# eco_mthbrd_REV_C1_sch.net
KiCad netlist of a schematic drawn in Altium Designer
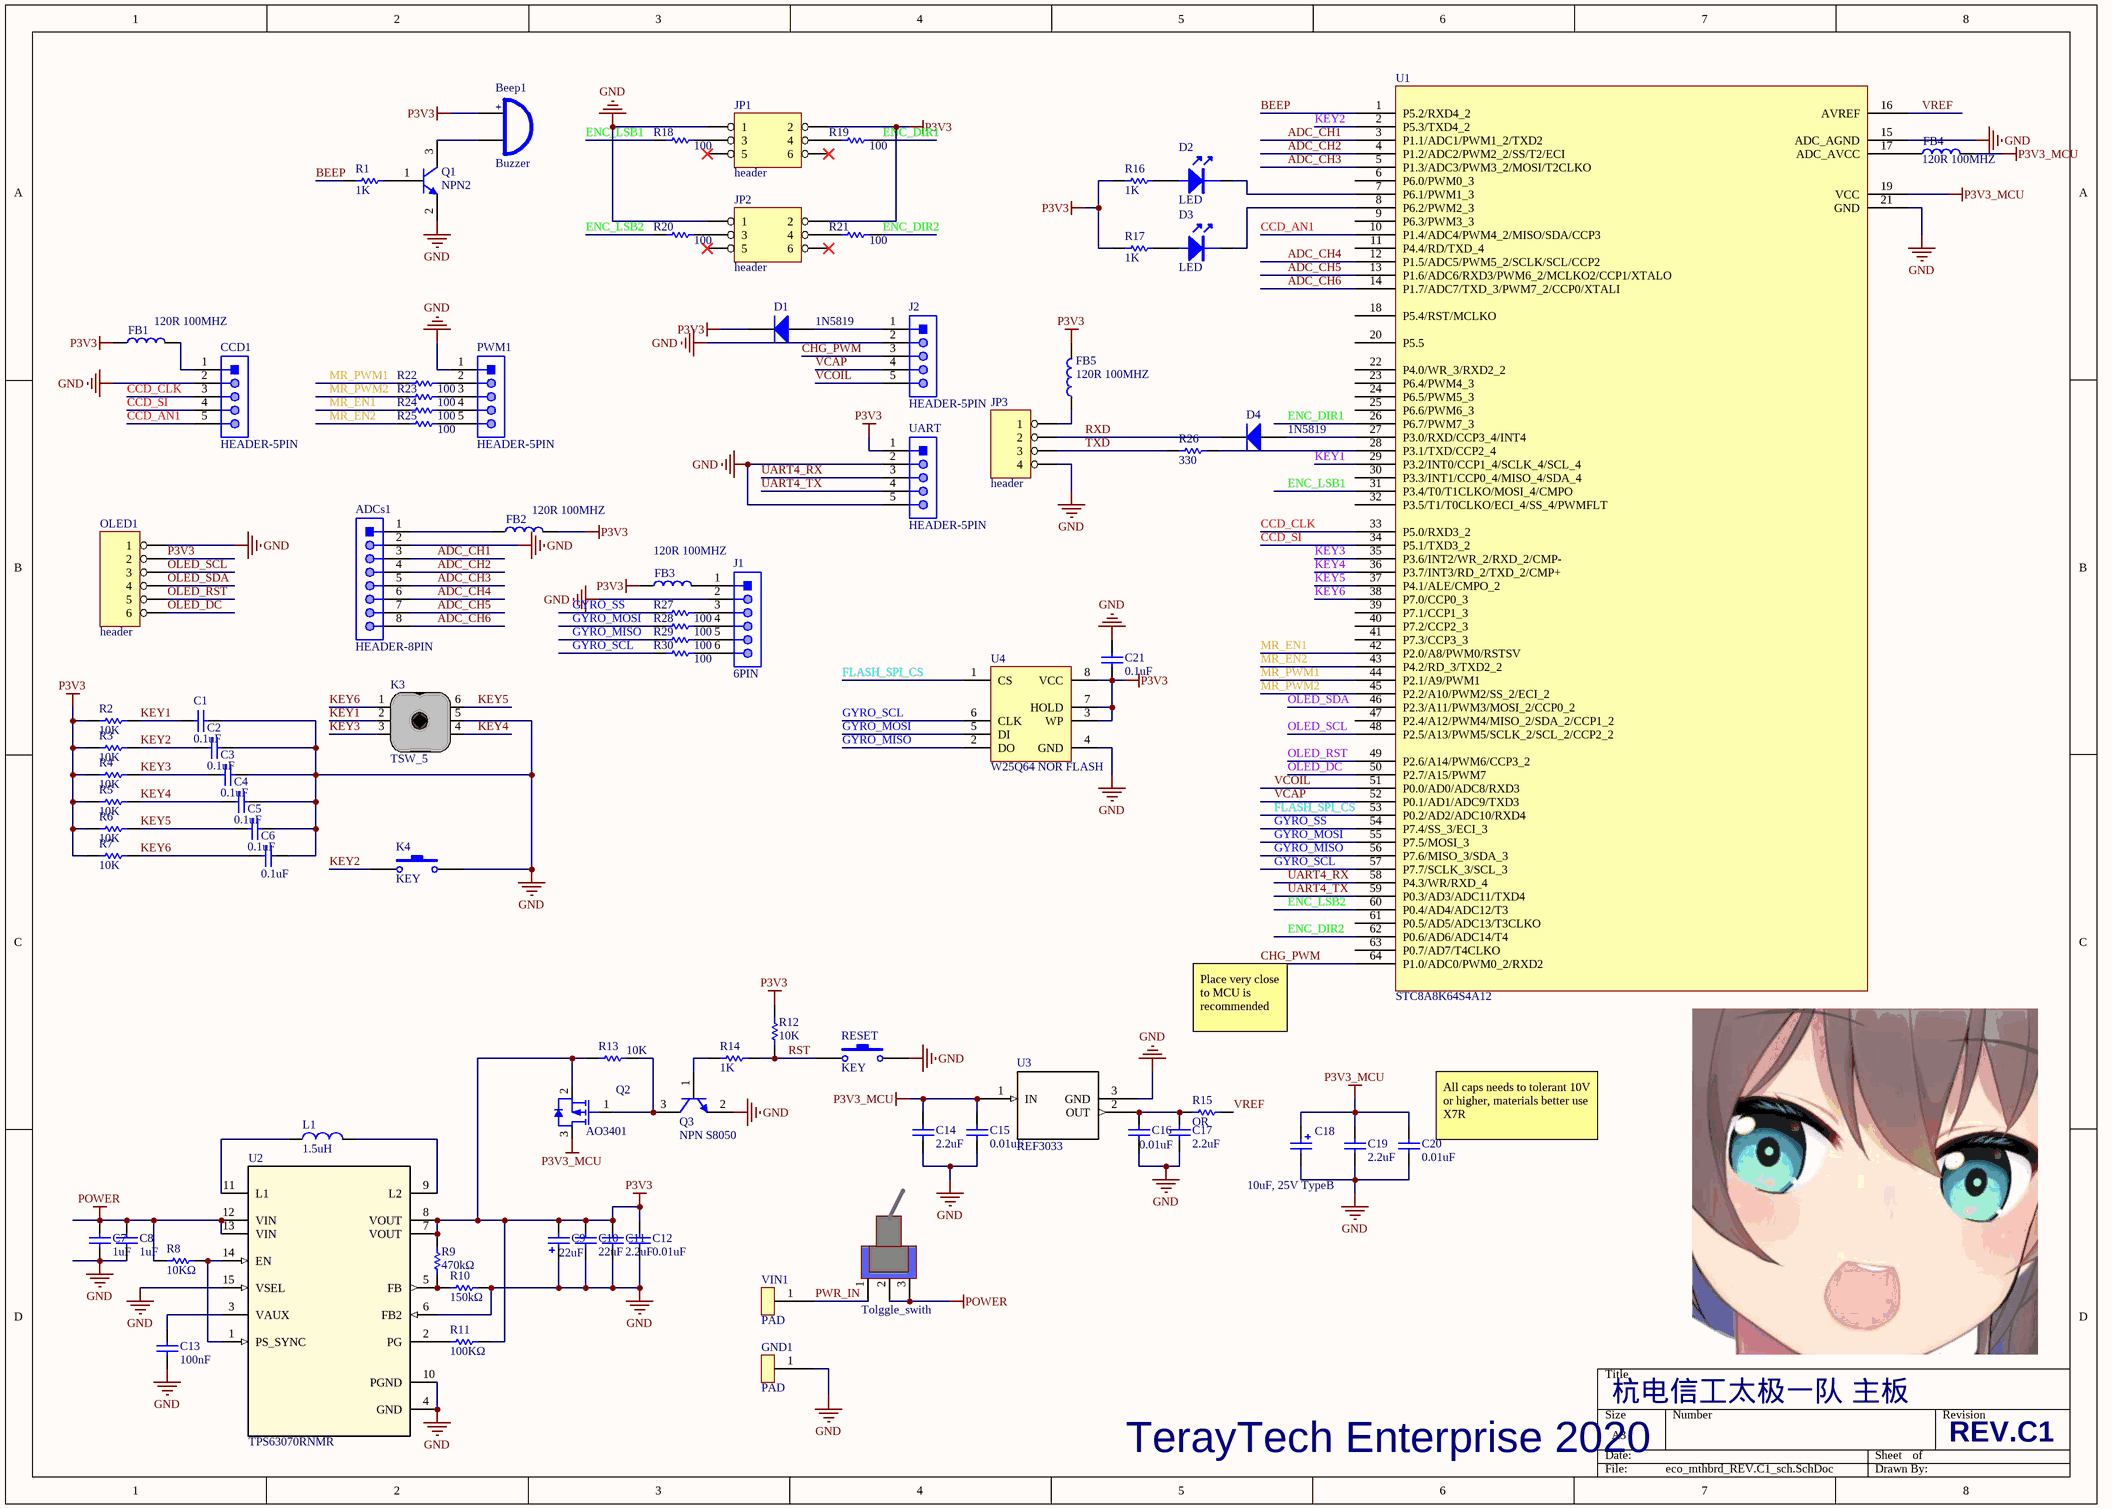
[diagram p0: eco_mthbrd_REV.C1_sch.SchDoc]

(export (version "E")
  (design (tool "Eeschema 10.0.6"))
  (components
    (comp (ref "ADCs1")
      (value "HEADER-8PIN")
      (footprint "HEADER_8P_1.25_RT")
      (libsource (lib "My Footprint") (part "HEADER-8PIN"))
    )
    (comp (ref "Beep1")
      (value "Buzzer")
      (footprint "BUZZER_9.6*9.6*5mm")
      (libsource (lib "My Footprint") (part "Buzzer"))
    )
    (comp (ref "C1")
      (value "0.1uF")
      (footprint "0603_C")
      (description "Capacitor")
      (fields (field (name "PUBLISHER") "Altium Limited"))
      (libsource (lib "My Footprint") (part "CAP"))
    )
    (comp (ref "C2")
      (value "0.1uF")
      (footprint "0603_C")
      (description "Capacitor")
      (fields (field (name "PUBLISHER") "Altium Limited"))
      (libsource (lib "My Footprint") (part "CAP"))
    )
    (comp (ref "C3")
      (value "0.1uF")
      (footprint "0603_C")
      (description "Capacitor")
      (fields (field (name "PUBLISHER") "Altium Limited"))
      (libsource (lib "My Footprint") (part "CAP"))
    )
    (comp (ref "C4")
      (value "0.1uF")
      (footprint "0603_C")
      (description "Capacitor")
      (fields (field (name "PUBLISHER") "Altium Limited"))
      (libsource (lib "My Footprint") (part "CAP"))
    )
    (comp (ref "C5")
      (value "0.1uF")
      (footprint "0603_C")
      (description "Capacitor")
      (fields (field (name "PUBLISHER") "Altium Limited"))
      (libsource (lib "My Footprint") (part "CAP"))
    )
    (comp (ref "C6")
      (value "0.1uF")
      (footprint "0603_C")
      (description "Capacitor")
      (fields (field (name "PUBLISHER") "Altium Limited"))
      (libsource (lib "My Footprint") (part "CAP"))
    )
    (comp (ref "C7")
      (value "1uF")
      (footprint "C1206")
      (description "Capacitor")
      (fields (field (name "PUBLISHER") "Altium Limited"))
      (libsource (lib "My Footprint") (part "CAP"))
    )
    (comp (ref "C8")
      (value "1uF")
      (footprint "0603_C")
      (description "Capacitor")
      (fields (field (name "PUBLISHER") "Altium Limited"))
      (libsource (lib "My Footprint") (part "CAP"))
    )
    (comp (ref "C9")
      (value "22uF")
      (footprint "CAPC3528B")
      (description "Capacitor")
      (fields (field (name "PUBLISHER") "Altium Limited"))
      (libsource (lib "My Footprint") (part "CAP_tan"))
    )
    (comp (ref "C10")
      (value "22uF")
      (footprint "C1206")
      (description "Capacitor")
      (fields (field (name "PUBLISHER") "Altium Limited"))
      (libsource (lib "My Footprint") (part "CAP"))
    )
    (comp (ref "C11")
      (value "2.2uF")
      (footprint "0603_C")
      (description "Capacitor")
      (fields (field (name "PUBLISHER") "Altium Limited"))
      (libsource (lib "My Footprint") (part "CAP"))
    )
    (comp (ref "C12")
      (value "0.01uF")
      (footprint "0603_C")
      (description "Capacitor")
      (fields (field (name "PUBLISHER") "Altium Limited"))
      (libsource (lib "My Footprint") (part "CAP"))
    )
    (comp (ref "C13")
      (value "100nF")
      (footprint "0603_C")
      (description "Capacitor")
      (fields (field (name "PUBLISHER") "Altium Limited"))
      (libsource (lib "My Footprint") (part "CAP"))
    )
    (comp (ref "C14")
      (value "2.2uF")
      (footprint "0603_C")
      (description "Capacitor")
      (fields (field (name "PUBLISHER") "Altium Limited"))
      (libsource (lib "My Footprint") (part "CAP"))
    )
    (comp (ref "C15")
      (value "0.01uF")
      (footprint "0603_C")
      (description "Capacitor")
      (fields (field (name "PUBLISHER") "Altium Limited"))
      (libsource (lib "My Footprint") (part "CAP"))
    )
    (comp (ref "C16")
      (value "0.01uF")
      (footprint "0603_C")
      (description "Capacitor")
      (fields (field (name "PUBLISHER") "Altium Limited"))
      (libsource (lib "My Footprint") (part "CAP"))
    )
    (comp (ref "C17")
      (value "2.2uF")
      (footprint "0603_C")
      (description "Capacitor")
      (fields (field (name "PUBLISHER") "Altium Limited"))
      (libsource (lib "My Footprint") (part "CAP"))
    )
    (comp (ref "C18")
      (value "10uF, 25V TypeB")
      (footprint "CAPC3528B")
      (description "Capacitor")
      (fields (field (name "PUBLISHER") "Altium Limited"))
      (libsource (lib "My Footprint") (part "CAP_tan"))
    )
    (comp (ref "C19")
      (value "2.2uF")
      (footprint "0603_C")
      (description "Capacitor")
      (fields (field (name "PUBLISHER") "Altium Limited"))
      (libsource (lib "My Footprint") (part "CAP"))
    )
    (comp (ref "C20")
      (value "0.01uF")
      (footprint "0603_C")
      (description "Capacitor")
      (fields (field (name "PUBLISHER") "Altium Limited"))
      (libsource (lib "My Footprint") (part "CAP"))
    )
    (comp (ref "C21")
      (value "0.1uF")
      (footprint "0603_C")
      (description "Capacitor")
      (fields (field (name "PUBLISHER") "Altium Limited"))
      (libsource (lib "My Footprint") (part "CAP"))
    )
    (comp (ref "CCD1")
      (value "HEADER-5PIN")
      (footprint "HEADER_5P_1.25_up")
      (libsource (lib "My Footprint") (part "HEADER-5PIN"))
    )
    (comp (ref "D1")
      (value "1N5819")
      (footprint "SOD123")
      (description "40V 1A PEAK 25a")
      (libsource (lib "My Footprint") (part "1N5819"))
    )
    (comp (ref "D2")
      (value "LED")
      (footprint "0603_LED")
      (description "LED 发光二极管")
      (libsource (lib "My Footprint") (part "LED"))
    )
    (comp (ref "D3")
      (value "LED")
      (footprint "0603_LED")
      (description "LED 发光二极管")
      (libsource (lib "My Footprint") (part "LED"))
    )
    (comp (ref "D4")
      (value "1N5819")
      (footprint "SOD123")
      (description "40V 1A PEAK 25a")
      (libsource (lib "My Footprint") (part "1N5819"))
    )
    (comp (ref "Energy1")
      (value "Tolggle_swith")
      (footprint "TOGGLE SWICH STAND")
      (libsource (lib "SamacSys") (part "Tolggle_swith"))
    )
    (comp (ref "FB1")
      (value "120R 100MHZ")
      (footprint "FB0603")
      (description "120OHM@100MHZ 2A 25% 0603")
      (libsource (lib "My Footprint") (part "FB"))
    )
    (comp (ref "FB2")
      (value "120R 100MHZ")
      (footprint "FB0603")
      (description "120OHM@100MHZ 2A 25% 0603")
      (libsource (lib "My Footprint") (part "FB"))
    )
    (comp (ref "FB3")
      (value "120R 100MHZ")
      (footprint "FB0603")
      (description "120OHM@100MHZ 2A 25% 0603")
      (libsource (lib "My Footprint") (part "FB"))
    )
    (comp (ref "FB4")
      (value "120R 100MHZ")
      (footprint "FB0603")
      (description "120OHM@100MHZ 2A 25% 0603")
      (libsource (lib "My Footprint") (part "FB"))
    )
    (comp (ref "FB5")
      (value "120R 100MHZ")
      (footprint "FB0603")
      (description "120OHM@100MHZ 2A 25% 0603")
      (libsource (lib "My Footprint") (part "FB"))
    )
    (comp (ref "GND1") (value "PAD") (footprint "PAD") (libsource (lib "My Footprint") (part "PAD")))
    (comp (ref "J1")
      (value "6PIN")
      (footprint "MX 1.25-WS-6P")
      (libsource (lib "My Footprint") (part "HEADER-6PIN"))
    )
    (comp (ref "J2")
      (value "HEADER-5PIN")
      (footprint "HEADER_5P_1.25_RT")
      (libsource (lib "My Footprint") (part "HEADER-5PIN"))
    )
    (comp (ref "JP1")
      (value "header")
      (footprint "header2X3")
      (libsource (lib "My Footprint") (part "HEADER 3X2"))
    )
    (comp (ref "JP2")
      (value "header")
      (footprint "header2X3")
      (libsource (lib "My Footprint") (part "HEADER 3X2"))
    )
    (comp (ref "JP3")
      (value "header")
      (footprint "header4")
      (libsource (lib "My Footprint") (part "HEADER 4"))
    )
    (comp (ref "K3")
      (value "TSW_5")
      (footprint "TSW-10")
      (description "方向开关")
      (libsource (lib "My Footprint") (part "TSW_5"))
    )
    (comp (ref "K4")
      (value "KEY")
      (footprint "贴片复位开关")
      (description "Switch")
      (fields (field (name "PUBLISHER") "Altium Limited"))
      (libsource (lib "My Footprint") (part "KEY_2"))
    )
    (comp (ref "L1") (value "1.5uH") (footprint "L 5x5") (libsource (lib "My Footprint") (part "Inductor")))
    (comp (ref "OLED1")
      (value "header")
      (footprint "0.96寸OLED模块")
      (libsource (lib "My Footprint") (part "HEADER 6"))
    )
    (comp (ref "PWM1")
      (value "HEADER-5PIN")
      (footprint "HEADER_5P_1.25_RT")
      (libsource (lib "My Footprint") (part "HEADER-5PIN"))
    )
    (comp (ref "Q1")
      (value "NPN2")
      (footprint "SOT-23-3")
      (description "贴片")
      (libsource (lib "My Footprint") (part "NPN2"))
    )
    (comp (ref "Q2")
      (value "AO3401")
      (footprint "SOT-23-3")
      (libsource (lib "SamacSys") (part "p-MOSEFT_SMALL"))
    )
    (comp (ref "Q3")
      (value "NPN S8050")
      (footprint "SOT-23-3")
      (description "贴片")
      (libsource (lib "My Footprint") (part "NPN2"))
    )
    (comp (ref "R1")
      (value "1K")
      (footprint "0603_R")
      (description "Resistor")
      (fields (field (name "PUBLISHER") "Altium Limited"))
      (libsource (lib "My Footprint") (part "RES"))
    )
    (comp (ref "R2")
      (value "10K")
      (footprint "0603_R")
      (description "Resistor")
      (fields (field (name "PUBLISHER") "Altium Limited"))
      (libsource (lib "My Footprint") (part "RES0"))
    )
    (comp (ref "R3")
      (value "10K")
      (footprint "0603_R")
      (description "Resistor")
      (fields (field (name "PUBLISHER") "Altium Limited"))
      (libsource (lib "My Footprint") (part "RES0"))
    )
    (comp (ref "R4")
      (value "10K")
      (footprint "0603_R")
      (description "Resistor")
      (fields (field (name "PUBLISHER") "Altium Limited"))
      (libsource (lib "My Footprint") (part "RES0"))
    )
    (comp (ref "R5")
      (value "10K")
      (footprint "0603_R")
      (description "Resistor")
      (fields (field (name "PUBLISHER") "Altium Limited"))
      (libsource (lib "My Footprint") (part "RES0"))
    )
    (comp (ref "R6")
      (value "10K")
      (footprint "0603_R")
      (description "Resistor")
      (fields (field (name "PUBLISHER") "Altium Limited"))
      (libsource (lib "My Footprint") (part "RES0"))
    )
    (comp (ref "R7")
      (value "10K")
      (footprint "0603_R")
      (description "Resistor")
      (fields (field (name "PUBLISHER") "Altium Limited"))
      (libsource (lib "My Footprint") (part "RES0"))
    )
    (comp (ref "R8")
      (value "10KΩ")
      (footprint "0603_R")
      (description "Resistor")
      (fields (field (name "PUBLISHER") "Altium Limited"))
      (libsource (lib "My Footprint") (part "RES0"))
    )
    (comp (ref "R9")
      (value "470kΩ")
      (footprint "0603_R")
      (description "Resistor")
      (fields (field (name "PUBLISHER") "Altium Limited"))
      (libsource (lib "My Footprint") (part "RES0"))
    )
    (comp (ref "R10")
      (value "150kΩ")
      (footprint "0603_R")
      (description "Resistor")
      (fields (field (name "PUBLISHER") "Altium Limited"))
      (libsource (lib "My Footprint") (part "RES0"))
    )
    (comp (ref "R11")
      (value "100KΩ")
      (footprint "0603_R")
      (description "Resistor")
      (fields (field (name "PUBLISHER") "Altium Limited"))
      (libsource (lib "My Footprint") (part "RES0"))
    )
    (comp (ref "R12")
      (value "10K")
      (footprint "0603_R")
      (description "Resistor")
      (fields (field (name "PUBLISHER") "Altium Limited"))
      (libsource (lib "My Footprint") (part "RES0"))
    )
    (comp (ref "R13")
      (value "10K")
      (footprint "0603_R")
      (description "Resistor")
      (fields (field (name "PUBLISHER") "Altium Limited"))
      (libsource (lib "My Footprint") (part "RES0"))
    )
    (comp (ref "R14")
      (value "1K")
      (footprint "0603_R")
      (description "Resistor")
      (fields (field (name "PUBLISHER") "Altium Limited"))
      (libsource (lib "My Footprint") (part "RES0"))
    )
    (comp (ref "R15")
      (value "OR")
      (footprint "0603_R")
      (description "Resistor")
      (fields (field (name "PUBLISHER") "Altium Limited"))
      (libsource (lib "My Footprint") (part "RES0"))
    )
    (comp (ref "R16")
      (value "1K")
      (footprint "0603_R")
      (description "Resistor")
      (fields (field (name "PUBLISHER") "Altium Limited"))
      (libsource (lib "My Footprint") (part "RES0"))
    )
    (comp (ref "R17")
      (value "1K")
      (footprint "0603_R")
      (description "Resistor")
      (fields (field (name "PUBLISHER") "Altium Limited"))
      (libsource (lib "My Footprint") (part "RES0"))
    )
    (comp (ref "R18")
      (value "100")
      (footprint "0603_R")
      (description "Resistor")
      (fields (field (name "PUBLISHER") "Altium Limited"))
      (libsource (lib "My Footprint") (part "RES0"))
    )
    (comp (ref "R19")
      (value "100")
      (footprint "0603_R")
      (description "Resistor")
      (fields (field (name "PUBLISHER") "Altium Limited"))
      (libsource (lib "My Footprint") (part "RES0"))
    )
    (comp (ref "R20")
      (value "100")
      (footprint "0603_R")
      (description "Resistor")
      (fields (field (name "PUBLISHER") "Altium Limited"))
      (libsource (lib "My Footprint") (part "RES0"))
    )
    (comp (ref "R21")
      (value "100")
      (footprint "0603_R")
      (description "Resistor")
      (fields (field (name "PUBLISHER") "Altium Limited"))
      (libsource (lib "My Footprint") (part "RES0"))
    )
    (comp (ref "R22")
      (value "100")
      (footprint "0603_R")
      (description "Resistor")
      (fields (field (name "PUBLISHER") "Altium Limited"))
      (libsource (lib "My Footprint") (part "RES0"))
    )
    (comp (ref "R23")
      (value "100")
      (footprint "0603_R")
      (description "Resistor")
      (fields (field (name "PUBLISHER") "Altium Limited"))
      (libsource (lib "My Footprint") (part "RES0"))
    )
    (comp (ref "R24")
      (value "100")
      (footprint "0603_R")
      (description "Resistor")
      (fields (field (name "PUBLISHER") "Altium Limited"))
      (libsource (lib "My Footprint") (part "RES0"))
    )
    (comp (ref "R25")
      (value "100")
      (footprint "0603_R")
      (description "Resistor")
      (fields (field (name "PUBLISHER") "Altium Limited"))
      (libsource (lib "My Footprint") (part "RES0"))
    )
    (comp (ref "R26")
      (value "330")
      (footprint "0603_R")
      (description "Resistor")
      (fields (field (name "PUBLISHER") "Altium Limited"))
      (libsource (lib "My Footprint") (part "RES0"))
    )
    (comp (ref "R27")
      (value "100")
      (footprint "0603_R")
      (description "Resistor")
      (fields (field (name "PUBLISHER") "Altium Limited"))
      (libsource (lib "My Footprint") (part "RES0"))
    )
    (comp (ref "R28")
      (value "100")
      (footprint "0603_R")
      (description "Resistor")
      (fields (field (name "PUBLISHER") "Altium Limited"))
      (libsource (lib "My Footprint") (part "RES0"))
    )
    (comp (ref "R29")
      (value "100")
      (footprint "0603_R")
      (description "Resistor")
      (fields (field (name "PUBLISHER") "Altium Limited"))
      (libsource (lib "My Footprint") (part "RES0"))
    )
    (comp (ref "R30")
      (value "100")
      (footprint "0603_R")
      (description "Resistor")
      (fields (field (name "PUBLISHER") "Altium Limited"))
      (libsource (lib "My Footprint") (part "RES0"))
    )
    (comp (ref "RESET")
      (value "KEY")
      (footprint "KEY_2")
      (description "Switch")
      (fields (field (name "PUBLISHER") "Altium Limited"))
      (libsource (lib "My Footprint") (part "KEY_2"))
    )
    (comp (ref "U1")
      (value "STC8A8K64S4A12")
      (footprint "TQFP64")
      (libsource (lib "SamacSys") (part "STC8A8K64S4A12_LQFP64"))
    )
    (comp (ref "U2")
      (value "TPS63070RNMR")
      (footprint "RNM0015A")
      (description "Imported")
      (fields (field (name "MANUFACTURER") "Texas Instruments"))
      (libsource (lib "SamacSys") (part "TPS63070RNMR"))
    )
    (comp (ref "U3")
      (value "REF3033")
      (footprint "DBZ3")
      (description "Imported")
      (fields
        (field (name "MANUFACTURER") "Texas Instruments")
        (field (name "MANUFACTURER_PART_NUMBER") "ref3033_dbz_3")
      )
      (libsource (lib "My Footprint") (part "REF3033_DBZ_3"))
    )
    (comp (ref "U4")
      (value "W25Q64 NOR FLASH")
      (footprint "SOIC8")
      (libsource (lib "My Footprint") (part "w25qxx"))
    )
    (comp (ref "UART")
      (value "HEADER-5PIN")
      (footprint "HEADER_5P_1.25_RT")
      (libsource (lib "My Footprint") (part "HEADER-5PIN"))
    )
    (comp (ref "VIN1") (value "PAD") (footprint "PAD") (libsource (lib "My Footprint") (part "PAD")))
  )
  (nets
    (net (code "1") (name "/ADC_CH1") (class "Default")
      (node (ref "ADCs1") (pin "3") (pinfunction "3_3") (pintype "passive"))
      (node (ref "U1") (pin "3") (pinfunction "P1.1/ADC1/PWM1_2/TXD2_3") (pintype "passive"))
    )
    (net (code "2") (name "/ADC_CH2") (class "Default")
      (node (ref "ADCs1") (pin "4") (pinfunction "4_4") (pintype "passive"))
      (node (ref "U1") (pin "4") (pinfunction "P1.2/ADC2/PWM2_2/SS/T2/ECI_4") (pintype "passive"))
    )
    (net (code "3") (name "/ADC_CH3") (class "Default")
      (node (ref "ADCs1") (pin "5") (pinfunction "5_5") (pintype "passive"))
      (node (ref "U1") (pin "5") (pinfunction "P1.3/ADC3/PWM3_2/MOSI/T2CLKO_5") (pintype "passive"))
    )
    (net (code "4") (name "/ADC_CH4") (class "Default")
      (node (ref "ADCs1") (pin "6") (pinfunction "6_6") (pintype "passive"))
      (node (ref "U1") (pin "12") (pinfunction "P1.5/ADC5/PWM5_2/SCLK/SCL/CCP2_12") (pintype "passive"))
    )
    (net (code "5") (name "/ADC_CH5") (class "Default")
      (node (ref "ADCs1") (pin "7") (pinfunction "7_7") (pintype "passive"))
      (node (ref "U1") (pin "13") (pinfunction "P1.6/ADC6/RXD3/PWM6_2/MCLKO2/CCP1/XTALO_13") (pintype "passive"))
    )
    (net (code "6") (name "/ADC_CH6") (class "Default")
      (node (ref "ADCs1") (pin "8") (pinfunction "8_8") (pintype "passive"))
      (node (ref "U1") (pin "14") (pinfunction "P1.7/ADC7/TXD_3/PWM7_2/CCP0/XTALI_14") (pintype "passive"))
    )
    (net (code "7") (name "/BEEP") (class "Default")
      (node (ref "R1") (pin "1") (pinfunction "1_1") (pintype "passive"))
      (node (ref "U1") (pin "1") (pinfunction "P5.2/RXD4_2_1") (pintype "passive"))
    )
    (net (code "8") (name "/CCD_AN1") (class "Default")
      (node (ref "CCD1") (pin "5") (pinfunction "5_5") (pintype "passive"))
      (node (ref "U1") (pin "10") (pinfunction "P1.4/ADC4/PWM4_2/MISO/SDA/CCP3_10") (pintype "passive"))
    )
    (net (code "9") (name "/CCD_CLK") (class "Default")
      (node (ref "CCD1") (pin "3") (pinfunction "3_3") (pintype "passive"))
      (node (ref "U1") (pin "33") (pinfunction "P5.0/RXD3_2_33") (pintype "passive"))
    )
    (net (code "10") (name "/CCD_SI") (class "Default")
      (node (ref "CCD1") (pin "4") (pinfunction "4_4") (pintype "passive"))
      (node (ref "U1") (pin "34") (pinfunction "P5.1/TXD3_2_34") (pintype "passive"))
    )
    (net (code "11") (name "/CHG_PWM") (class "Default")
      (node (ref "J2") (pin "3") (pinfunction "3_3") (pintype "passive"))
      (node (ref "U1") (pin "64") (pinfunction "P1.0/ADC0/PWM0_2/RXD2_64") (pintype "passive"))
    )
    (net (code "12") (name "/ENC_DIR1") (class "Default")
      (node (ref "R19") (pin "2") (pinfunction "2_2") (pintype "passive"))
      (node (ref "U1") (pin "26") (pinfunction "P6.7/PWM7_3_26") (pintype "passive"))
    )
    (net (code "13") (name "/ENC_DIR2") (class "Default")
      (node (ref "R21") (pin "2") (pinfunction "2_2") (pintype "passive"))
      (node (ref "U1") (pin "62") (pinfunction "P0.6/AD6/ADC14/T4_62") (pintype "passive"))
    )
    (net (code "14") (name "/ENC_LSB1") (class "Default")
      (node (ref "R18") (pin "1") (pinfunction "1_1") (pintype "passive"))
      (node (ref "U1") (pin "31") (pinfunction "P3.4/T0/T1CLKO/MOSI_4/CMPO_31") (pintype "passive"))
    )
    (net (code "15") (name "/ENC_LSB2") (class "Default")
      (node (ref "R20") (pin "1") (pinfunction "1_1") (pintype "passive"))
      (node (ref "U1") (pin "60") (pinfunction "P0.4/AD4/ADC12/T3_60") (pintype "passive"))
    )
    (net (code "16") (name "/FLASH_SPI_CS") (class "Default")
      (node (ref "U1") (pin "53") (pinfunction "P0.2/AD2/ADC10/RXD4_53") (pintype "passive"))
      (node (ref "U4") (pin "1") (pinfunction "CS_1") (pintype "passive"))
    )
    (net (code "17") (name "/GYRO_MISO") (class "Default")
      (node (ref "R29") (pin "1") (pinfunction "1_1") (pintype "passive"))
      (node (ref "U1") (pin "56") (pinfunction "P7.6/MISO_3/SDA_3_56") (pintype "passive"))
      (node (ref "U4") (pin "2") (pinfunction "DO_2") (pintype "passive"))
    )
    (net (code "18") (name "/GYRO_MOSI") (class "Default")
      (node (ref "R28") (pin "1") (pinfunction "1_1") (pintype "passive"))
      (node (ref "U1") (pin "55") (pinfunction "P7.5/MOSI_3_55") (pintype "passive"))
      (node (ref "U4") (pin "5") (pinfunction "DI_5") (pintype "passive"))
    )
    (net (code "19") (name "/GYRO_SCL") (class "Default")
      (node (ref "R30") (pin "1") (pinfunction "1_1") (pintype "passive"))
      (node (ref "U1") (pin "57") (pinfunction "P7.7/SCLK_3/SCL_3_57") (pintype "passive"))
      (node (ref "U4") (pin "6") (pinfunction "CLK_6") (pintype "passive"))
    )
    (net (code "20") (name "/GYRO_SS") (class "Default")
      (node (ref "R27") (pin "1") (pinfunction "1_1") (pintype "passive"))
      (node (ref "U1") (pin "54") (pinfunction "P7.4/SS_3/ECI_3_54") (pintype "passive"))
    )
    (net (code "21") (name "/KEY1") (class "Default")
      (node (ref "C1") (pin "1") (pinfunction "1_1") (pintype "passive"))
      (node (ref "K3") (pin "2") (pintype "passive"))
      (node (ref "R2") (pin "2") (pinfunction "2_2") (pintype "passive"))
      (node (ref "U1") (pin "29") (pinfunction "P3.2/INT0/CCP1_4/SCLK_4/SCL_4_29") (pintype "passive"))
    )
    (net (code "22") (name "/KEY2") (class "Default")
      (node (ref "C2") (pin "1") (pinfunction "1_1") (pintype "passive"))
      (node (ref "K4") (pin "1") (pinfunction "1_1") (pintype "passive"))
      (node (ref "R3") (pin "2") (pinfunction "2_2") (pintype "passive"))
      (node (ref "U1") (pin "2") (pinfunction "P5.3/TXD4_2_2") (pintype "passive"))
    )
    (net (code "23") (name "/KEY3") (class "Default")
      (node (ref "C3") (pin "1") (pinfunction "1_1") (pintype "passive"))
      (node (ref "K3") (pin "3") (pintype "passive"))
      (node (ref "R4") (pin "2") (pinfunction "2_2") (pintype "passive"))
      (node (ref "U1") (pin "35") (pinfunction "P3.6/INT2/WR_2/RXD_2/CMP-_35") (pintype "passive"))
    )
    (net (code "24") (name "/KEY4") (class "Default")
      (node (ref "C4") (pin "1") (pinfunction "1_1") (pintype "passive"))
      (node (ref "K3") (pin "4") (pintype "passive"))
      (node (ref "R5") (pin "2") (pinfunction "2_2") (pintype "passive"))
      (node (ref "U1") (pin "36") (pinfunction "P3.7/INT3/RD_2/TXD_2/CMP+_36") (pintype "passive"))
    )
    (net (code "25") (name "/KEY5") (class "Default")
      (node (ref "C5") (pin "1") (pinfunction "1_1") (pintype "passive"))
      (node (ref "K3") (pin "6") (pintype "passive"))
      (node (ref "R6") (pin "2") (pinfunction "2_2") (pintype "passive"))
      (node (ref "U1") (pin "37") (pinfunction "P4.1/ALE/CMPO_2_37") (pintype "passive"))
    )
    (net (code "26") (name "/KEY6") (class "Default")
      (node (ref "C6") (pin "1") (pinfunction "1_1") (pintype "passive"))
      (node (ref "K3") (pin "1") (pintype "passive"))
      (node (ref "R7") (pin "2") (pinfunction "2_2") (pintype "passive"))
      (node (ref "U1") (pin "38") (pinfunction "P7.0/CCP0_3_38") (pintype "passive"))
    )
    (net (code "27") (name "/MR_EN1") (class "Default")
      (node (ref "R24") (pin "1") (pinfunction "1_1") (pintype "passive"))
      (node (ref "U1") (pin "42") (pinfunction "P2.0/A8/PWM0/RSTSV_42") (pintype "passive"))
    )
    (net (code "28") (name "/MR_EN2") (class "Default")
      (node (ref "R25") (pin "1") (pinfunction "1_1") (pintype "passive"))
      (node (ref "U1") (pin "43") (pinfunction "P4.2/RD_3/TXD2_2_43") (pintype "passive"))
    )
    (net (code "29") (name "/MR_PWM1") (class "Default")
      (node (ref "R22") (pin "1") (pinfunction "1_1") (pintype "passive"))
      (node (ref "U1") (pin "44") (pinfunction "P2.1/A9/PWM1_44") (pintype "passive"))
    )
    (net (code "30") (name "/MR_PWM2") (class "Default")
      (node (ref "R23") (pin "1") (pinfunction "1_1") (pintype "passive"))
      (node (ref "U1") (pin "45") (pinfunction "P2.2/A10/PWM2/SS_2/ECI_2_45") (pintype "passive"))
    )
    (net (code "31") (name "/OLED_DC") (class "Default")
      (node (ref "OLED1") (pin "6") (pinfunction "6_6") (pintype "passive"))
      (node (ref "U1") (pin "50") (pinfunction "P2.7/A15/PWM7_50") (pintype "passive"))
    )
    (net (code "32") (name "/OLED_RST") (class "Default")
      (node (ref "OLED1") (pin "5") (pinfunction "5_5") (pintype "passive"))
      (node (ref "U1") (pin "49") (pinfunction "P2.6/A14/PWM6/CCP3_2_49") (pintype "passive"))
    )
    (net (code "33") (name "/OLED_SCL") (class "Default")
      (node (ref "OLED1") (pin "3") (pinfunction "3_3") (pintype "passive"))
      (node (ref "U1") (pin "48") (pinfunction "P2.5/A13/PWM5/SCLK_2/SCL_2/CCP2_2_48") (pintype "passive"))
    )
    (net (code "34") (name "/OLED_SDA") (class "Default")
      (node (ref "OLED1") (pin "4") (pinfunction "4_4") (pintype "passive"))
      (node (ref "U1") (pin "46") (pinfunction "P2.3/A11/PWM3/MOSI_2/CCP0_2_46") (pintype "passive"))
    )
    (net (code "35") (name "/PWR_IN") (class "Default")
      (node (ref "Energy1") (pin "1") (pintype "passive"))
      (node (ref "VIN1") (pin "1") (pintype "passive"))
    )
    (net (code "36") (name "/RST") (class "Default")
      (node (ref "R12") (pin "2") (pinfunction "2_2") (pintype "passive"))
      (node (ref "R14") (pin "2") (pinfunction "2_2") (pintype "passive"))
      (node (ref "RESET") (pin "1") (pinfunction "1_1") (pintype "passive"))
    )
    (net (code "37") (name "/RXD") (class "Default")
      (node (ref "D4") (pin "2") (pinfunction "K_2") (pintype "passive"))
      (node (ref "JP3") (pin "2") (pinfunction "2_2") (pintype "passive"))
    )
    (net (code "38") (name "/TXD") (class "Default")
      (node (ref "JP3") (pin "3") (pinfunction "3_3") (pintype "passive"))
      (node (ref "R26") (pin "1") (pinfunction "1_1") (pintype "passive"))
    )
    (net (code "39") (name "/UART4_RX") (class "Default")
      (node (ref "U1") (pin "58") (pinfunction "P4.3/WR/RXD_4_58") (pintype "passive"))
      (node (ref "UART") (pin "3") (pinfunction "3_3") (pintype "passive"))
    )
    (net (code "40") (name "/UART4_TX") (class "Default")
      (node (ref "U1") (pin "59") (pinfunction "P0.3/AD3/ADC11/TXD4_59") (pintype "passive"))
      (node (ref "UART") (pin "4") (pinfunction "4_4") (pintype "passive"))
    )
    (net (code "41") (name "/VCAP") (class "Default")
      (node (ref "J2") (pin "4") (pinfunction "4_4") (pintype "passive"))
      (node (ref "U1") (pin "52") (pinfunction "P0.1/AD1/ADC9/TXD3_52") (pintype "passive"))
    )
    (net (code "42") (name "/VCOIL") (class "Default")
      (node (ref "J2") (pin "5") (pinfunction "5_5") (pintype "passive"))
      (node (ref "U1") (pin "51") (pinfunction "P0.0/AD0/ADC8/RXD3_51") (pintype "passive"))
    )
    (net (code "43") (name "/VREF") (class "Default")
      (node (ref "R15") (pin "2") (pinfunction "2_2") (pintype "passive"))
      (node (ref "U1") (pin "16") (pinfunction "AVREF_16") (pintype "passive"))
    )
    (net (code "44") (name "GND") (class "Default")
      (node (ref "ADCs1") (pin "2") (pinfunction "2_2") (pintype "passive"))
      (node (ref "C1") (pin "2") (pinfunction "2_2") (pintype "passive"))
      (node (ref "C10") (pin "1") (pinfunction "1_1") (pintype "passive"))
      (node (ref "C11") (pin "1") (pinfunction "1_1") (pintype "passive"))
      (node (ref "C12") (pin "1") (pinfunction "1_1") (pintype "passive"))
      (node (ref "C13") (pin "1") (pinfunction "1_1") (pintype "passive"))
      (node (ref "C14") (pin "2") (pinfunction "2_2") (pintype "passive"))
      (node (ref "C15") (pin "2") (pinfunction "2_2") (pintype "passive"))
      (node (ref "C16") (pin "1") (pinfunction "1_1") (pintype "passive"))
      (node (ref "C17") (pin "1") (pinfunction "1_1") (pintype "passive"))
      (node (ref "C18") (pin "2") (pinfunction "2_2") (pintype "passive"))
      (node (ref "C19") (pin "1") (pinfunction "1_1") (pintype "passive"))
      (node (ref "C2") (pin "2") (pinfunction "2_2") (pintype "passive"))
      (node (ref "C20") (pin "1") (pinfunction "1_1") (pintype "passive"))
      (node (ref "C21") (pin "2") (pinfunction "2_2") (pintype "passive"))
      (node (ref "C3") (pin "2") (pinfunction "2_2") (pintype "passive"))
      (node (ref "C4") (pin "2") (pinfunction "2_2") (pintype "passive"))
      (node (ref "C5") (pin "2") (pinfunction "2_2") (pintype "passive"))
      (node (ref "C6") (pin "2") (pinfunction "2_2") (pintype "passive"))
      (node (ref "C7") (pin "1") (pinfunction "1_1") (pintype "passive"))
      (node (ref "C8") (pin "1") (pinfunction "1_1") (pintype "passive"))
      (node (ref "C9") (pin "1") (pinfunction "1_1") (pintype "passive"))
      (node (ref "CCD1") (pin "2") (pinfunction "2_2") (pintype "passive"))
      (node (ref "GND1") (pin "1") (pintype "passive"))
      (node (ref "J1") (pin "2") (pinfunction "2_2") (pintype "passive"))
      (node (ref "J2") (pin "2") (pinfunction "2_2") (pintype "passive"))
      (node (ref "JP1") (pin "1") (pinfunction "1_1") (pintype "passive"))
      (node (ref "JP2") (pin "1") (pinfunction "1_1") (pintype "passive"))
      (node (ref "JP3") (pin "4") (pinfunction "4_4") (pintype "passive"))
      (node (ref "K3") (pin "5") (pintype "passive"))
      (node (ref "K4") (pin "2") (pinfunction "2_2") (pintype "passive"))
      (node (ref "OLED1") (pin "1") (pinfunction "1_1") (pintype "passive"))
      (node (ref "PWM1") (pin "1") (pinfunction "1_1") (pintype "passive"))
      (node (ref "Q1") (pin "2") (pinfunction "E_2") (pintype "passive"))
      (node (ref "Q3") (pin "2") (pinfunction "E_2") (pintype "passive"))
      (node (ref "R10") (pin "1") (pinfunction "1_1") (pintype "passive"))
      (node (ref "RESET") (pin "2") (pinfunction "2_2") (pintype "passive"))
      (node (ref "U1") (pin "15") (pinfunction "ADC_AGND_15") (pintype "passive"))
      (node (ref "U1") (pin "21") (pinfunction "GND_21") (pintype "passive"))
      (node (ref "U2") (pin "10") (pinfunction "PGND_10") (pintype "power_in"))
      (node (ref "U2") (pin "15") (pinfunction "VSEL_15") (pintype "input"))
      (node (ref "U2") (pin "4") (pinfunction "GND_4") (pintype "power_in"))
      (node (ref "U2") (pin "6") (pinfunction "FB2_6") (pintype "input"))
      (node (ref "U3") (pin "3") (pinfunction "GND_3") (pintype "power_in"))
      (node (ref "U4") (pin "4") (pinfunction "GND_4") (pintype "passive"))
      (node (ref "UART") (pin "2") (pinfunction "2_2") (pintype "passive"))
      (node (ref "UART") (pin "5") (pinfunction "5_5") (pintype "passive"))
    )
    (net (code "45") (name "Net-(ADCs1-Pad1)") (class "Default")
      (node (ref "ADCs1") (pin "1") (pinfunction "1_1") (pintype "passive"))
      (node (ref "FB2") (pin "1") (pinfunction "1_1") (pintype "passive"))
    )
    (net (code "46") (name "Net-(Beep1-B)") (class "Default")
      (node (ref "Beep1") (pin "2") (pinfunction "B_2") (pintype "passive"))
      (node (ref "Q1") (pin "3") (pinfunction "C_3") (pintype "passive"))
    )
    (net (code "47") (name "Net-(CCD1-Pad1)") (class "Default")
      (node (ref "CCD1") (pin "1") (pinfunction "1_1") (pintype "passive"))
      (node (ref "FB1") (pin "2") (pinfunction "2_2") (pintype "passive"))
    )
    (net (code "48") (name "Net-(D1-A)") (class "Default")
      (node (ref "D1") (pin "1") (pinfunction "A_1") (pintype "passive"))
      (node (ref "J2") (pin "1") (pinfunction "1_1") (pintype "passive"))
    )
    (net (code "49") (name "Net-(D2-A)") (class "Default")
      (node (ref "D2") (pin "1") (pinfunction "A_1") (pintype "passive"))
      (node (ref "R16") (pin "2") (pinfunction "2_2") (pintype "passive"))
    )
    (net (code "50") (name "Net-(D2-K)") (class "Default")
      (node (ref "D2") (pin "2") (pinfunction "K_2") (pintype "passive"))
      (node (ref "U1") (pin "7") (pinfunction "P6.1/PWM1_3_7") (pintype "passive"))
    )
    (net (code "51") (name "Net-(D3-A)") (class "Default")
      (node (ref "D3") (pin "1") (pinfunction "A_1") (pintype "passive"))
      (node (ref "R17") (pin "2") (pinfunction "2_2") (pintype "passive"))
    )
    (net (code "52") (name "Net-(D3-K)") (class "Default")
      (node (ref "D3") (pin "2") (pinfunction "K_2") (pintype "passive"))
      (node (ref "U1") (pin "8") (pinfunction "P6.2/PWM2_3_8") (pintype "passive"))
    )
    (net (code "53") (name "Net-(D4-A)") (class "Default")
      (node (ref "D4") (pin "1") (pinfunction "A_1") (pintype "passive"))
      (node (ref "U1") (pin "27") (pinfunction "P3.0/RXD/CCP3_4/INT4_27") (pintype "passive"))
    )
    (net (code "54") (name "Net-(FB3-Pad2)") (class "Default")
      (node (ref "FB3") (pin "2") (pinfunction "2_2") (pintype "passive"))
      (node (ref "J1") (pin "1") (pinfunction "1_1") (pintype "passive"))
    )
    (net (code "55") (name "Net-(FB5-Pad1)") (class "Default")
      (node (ref "FB5") (pin "1") (pinfunction "1_1") (pintype "passive"))
      (node (ref "JP3") (pin "1") (pinfunction "1_1") (pintype "passive"))
    )
    (net (code "56") (name "Net-(J1-Pad3)") (class "Default")
      (node (ref "J1") (pin "3") (pinfunction "3_3") (pintype "passive"))
      (node (ref "R27") (pin "2") (pinfunction "2_2") (pintype "passive"))
    )
    (net (code "57") (name "Net-(J1-Pad4)") (class "Default")
      (node (ref "J1") (pin "4") (pinfunction "4_4") (pintype "passive"))
      (node (ref "R28") (pin "2") (pinfunction "2_2") (pintype "passive"))
    )
    (net (code "58") (name "Net-(J1-Pad5)") (class "Default")
      (node (ref "J1") (pin "5") (pinfunction "5_5") (pintype "passive"))
      (node (ref "R29") (pin "2") (pinfunction "2_2") (pintype "passive"))
    )
    (net (code "59") (name "Net-(J1-Pad6)") (class "Default")
      (node (ref "J1") (pin "6") (pinfunction "6_6") (pintype "passive"))
      (node (ref "R30") (pin "2") (pinfunction "2_2") (pintype "passive"))
    )
    (net (code "60") (name "Net-(JP1-Pad3)") (class "Default")
      (node (ref "JP1") (pin "3") (pinfunction "3_3") (pintype "passive"))
      (node (ref "R18") (pin "2") (pinfunction "2_2") (pintype "passive"))
    )
    (net (code "61") (name "Net-(JP1-Pad4)") (class "Default")
      (node (ref "JP1") (pin "4") (pinfunction "4_4") (pintype "passive"))
      (node (ref "R19") (pin "1") (pinfunction "1_1") (pintype "passive"))
    )
    (net (code "62") (name "Net-(JP2-Pad3)") (class "Default")
      (node (ref "JP2") (pin "3") (pinfunction "3_3") (pintype "passive"))
      (node (ref "R20") (pin "2") (pinfunction "2_2") (pintype "passive"))
    )
    (net (code "63") (name "Net-(JP2-Pad4)") (class "Default")
      (node (ref "JP2") (pin "4") (pinfunction "4_4") (pintype "passive"))
      (node (ref "R21") (pin "1") (pinfunction "1_1") (pintype "passive"))
    )
    (net (code "64") (name "Net-(PWM1-Pad2)") (class "Default")
      (node (ref "PWM1") (pin "2") (pinfunction "2_2") (pintype "passive"))
      (node (ref "R22") (pin "2") (pinfunction "2_2") (pintype "passive"))
    )
    (net (code "65") (name "Net-(PWM1-Pad3)") (class "Default")
      (node (ref "PWM1") (pin "3") (pinfunction "3_3") (pintype "passive"))
      (node (ref "R23") (pin "2") (pinfunction "2_2") (pintype "passive"))
    )
    (net (code "66") (name "Net-(PWM1-Pad4)") (class "Default")
      (node (ref "PWM1") (pin "4") (pinfunction "4_4") (pintype "passive"))
      (node (ref "R24") (pin "2") (pinfunction "2_2") (pintype "passive"))
    )
    (net (code "67") (name "Net-(PWM1-Pad5)") (class "Default")
      (node (ref "PWM1") (pin "5") (pinfunction "5_5") (pintype "passive"))
      (node (ref "R25") (pin "2") (pinfunction "2_2") (pintype "passive"))
    )
    (net (code "68") (name "Net-(Q1-B)") (class "Default")
      (node (ref "Q1") (pin "1") (pinfunction "B_1") (pintype "passive"))
      (node (ref "R1") (pin "2") (pinfunction "2_2") (pintype "passive"))
    )
    (net (code "69") (name "Net-(Q2-G)") (class "Default")
      (node (ref "Q2") (pin "1") (pinfunction "G_1") (pintype "passive"))
      (node (ref "Q3") (pin "3") (pinfunction "C_3") (pintype "passive"))
      (node (ref "R13") (pin "1") (pinfunction "1_1") (pintype "passive"))
    )
    (net (code "70") (name "Net-(Q3-B)") (class "Default")
      (node (ref "Q3") (pin "1") (pinfunction "B_1") (pintype "passive"))
      (node (ref "R14") (pin "1") (pinfunction "1_1") (pintype "passive"))
    )
    (net (code "71") (name "Net-(U1-ADC_AVCC)") (class "Default")
      (node (ref "FB4") (pin "1") (pinfunction "1_1") (pintype "passive"))
      (node (ref "U1") (pin "17") (pinfunction "ADC_AVCC_17") (pintype "passive"))
    )
    (net (code "72") (name "Net-(U1-P3.1{slash}TXD{slash}CCP2_4)") (class "Default")
      (node (ref "R26") (pin "2") (pinfunction "2_2") (pintype "passive"))
      (node (ref "U1") (pin "28") (pinfunction "P3.1/TXD/CCP2_4_28") (pintype "passive"))
    )
    (net (code "73") (name "Net-(U2-EN)") (class "Default")
      (node (ref "R8") (pin "1") (pinfunction "1_1") (pintype "passive"))
      (node (ref "U2") (pin "1") (pinfunction "PS_SYNC_1") (pintype "input"))
      (node (ref "U2") (pin "14") (pinfunction "EN_14") (pintype "input"))
    )
    (net (code "74") (name "Net-(U2-FB)") (class "Default")
      (node (ref "R10") (pin "2") (pinfunction "2_2") (pintype "passive"))
      (node (ref "R9") (pin "1") (pinfunction "1_1") (pintype "passive"))
      (node (ref "U2") (pin "5") (pinfunction "FB_5") (pintype "output"))
    )
    (net (code "75") (name "Net-(U2-L1)") (class "Default")
      (node (ref "L1") (pin "1") (pinfunction "1_1") (pintype "passive"))
      (node (ref "U2") (pin "11") (pinfunction "L1_11") (pintype "passive"))
    )
    (net (code "76") (name "Net-(U2-L2)") (class "Default")
      (node (ref "L1") (pin "2") (pinfunction "2_2") (pintype "passive"))
      (node (ref "U2") (pin "9") (pinfunction "L2_9") (pintype "passive"))
    )
    (net (code "77") (name "Net-(U2-PG)") (class "Default")
      (node (ref "R11") (pin "2") (pinfunction "2_2") (pintype "passive"))
      (node (ref "U2") (pin "2") (pinfunction "PG_2") (pintype "open_collector"))
    )
    (net (code "78") (name "Net-(U2-VAUX)") (class "Default")
      (node (ref "C13") (pin "2") (pinfunction "2_2") (pintype "passive"))
      (node (ref "U2") (pin "3") (pinfunction "VAUX_3") (pintype "passive"))
    )
    (net (code "79") (name "Net-(U3-OUT)") (class "Default")
      (node (ref "C16") (pin "2") (pinfunction "2_2") (pintype "passive"))
      (node (ref "C17") (pin "2") (pinfunction "2_2") (pintype "passive"))
      (node (ref "R15") (pin "1") (pinfunction "1_1") (pintype "passive"))
      (node (ref "U3") (pin "2") (pinfunction "OUT_2") (pintype "output"))
    )
    (net (code "80") (name "P3V3") (class "Default")
      (node (ref "Beep1") (pin "1") (pinfunction "A_1") (pintype "passive"))
      (node (ref "C10") (pin "2") (pinfunction "2_2") (pintype "passive"))
      (node (ref "C11") (pin "2") (pinfunction "2_2") (pintype "passive"))
      (node (ref "C12") (pin "2") (pinfunction "2_2") (pintype "passive"))
      (node (ref "C21") (pin "1") (pinfunction "1_1") (pintype "passive"))
      (node (ref "C9") (pin "2") (pinfunction "2_2") (pintype "passive"))
      (node (ref "D1") (pin "2") (pinfunction "K_2") (pintype "passive"))
      (node (ref "FB1") (pin "1") (pinfunction "1_1") (pintype "passive"))
      (node (ref "FB2") (pin "2") (pinfunction "2_2") (pintype "passive"))
      (node (ref "FB3") (pin "1") (pinfunction "1_1") (pintype "passive"))
      (node (ref "FB5") (pin "2") (pinfunction "2_2") (pintype "passive"))
      (node (ref "JP1") (pin "2") (pinfunction "2_2") (pintype "passive"))
      (node (ref "JP2") (pin "2") (pinfunction "2_2") (pintype "passive"))
      (node (ref "OLED1") (pin "2") (pinfunction "2_2") (pintype "passive"))
      (node (ref "Q2") (pin "2") (pinfunction "S_2") (pintype "passive"))
      (node (ref "R11") (pin "1") (pinfunction "1_1") (pintype "passive"))
      (node (ref "R12") (pin "1") (pinfunction "1_1") (pintype "passive"))
      (node (ref "R13") (pin "2") (pinfunction "2_2") (pintype "passive"))
      (node (ref "R16") (pin "1") (pinfunction "1_1") (pintype "passive"))
      (node (ref "R17") (pin "1") (pinfunction "1_1") (pintype "passive"))
      (node (ref "R2") (pin "1") (pinfunction "1_1") (pintype "passive"))
      (node (ref "R3") (pin "1") (pinfunction "1_1") (pintype "passive"))
      (node (ref "R4") (pin "1") (pinfunction "1_1") (pintype "passive"))
      (node (ref "R5") (pin "1") (pinfunction "1_1") (pintype "passive"))
      (node (ref "R6") (pin "1") (pinfunction "1_1") (pintype "passive"))
      (node (ref "R7") (pin "1") (pinfunction "1_1") (pintype "passive"))
      (node (ref "R9") (pin "2") (pinfunction "2_2") (pintype "passive"))
      (node (ref "U2") (pin "7") (pinfunction "VOUT_7") (pintype "power_in"))
      (node (ref "U2") (pin "8") (pinfunction "VOUT_8") (pintype "power_in"))
      (node (ref "U4") (pin "3") (pinfunction "WP_3") (pintype "passive"))
      (node (ref "U4") (pin "7") (pinfunction "HOLD_7") (pintype "passive"))
      (node (ref "U4") (pin "8") (pinfunction "VCC_8") (pintype "passive"))
      (node (ref "UART") (pin "1") (pinfunction "1_1") (pintype "passive"))
    )
    (net (code "81") (name "P3V3_MCU") (class "Default")
      (node (ref "C14") (pin "1") (pinfunction "1_1") (pintype "passive"))
      (node (ref "C15") (pin "1") (pinfunction "1_1") (pintype "passive"))
      (node (ref "C18") (pin "1") (pinfunction "1_1") (pintype "passive"))
      (node (ref "C19") (pin "2") (pinfunction "2_2") (pintype "passive"))
      (node (ref "C20") (pin "2") (pinfunction "2_2") (pintype "passive"))
      (node (ref "FB4") (pin "2") (pinfunction "2_2") (pintype "passive"))
      (node (ref "Q2") (pin "3") (pinfunction "D_3") (pintype "passive"))
      (node (ref "U1") (pin "19") (pinfunction "VCC_19") (pintype "passive"))
      (node (ref "U3") (pin "1") (pinfunction "IN_1") (pintype "input"))
    )
    (net (code "82") (name "POWER") (class "Default")
      (node (ref "C7") (pin "2") (pinfunction "2_2") (pintype "passive"))
      (node (ref "C8") (pin "2") (pinfunction "2_2") (pintype "passive"))
      (node (ref "Energy1") (pin "2") (pintype "passive"))
      (node (ref "Energy1") (pin "3") (pintype "passive"))
      (node (ref "R8") (pin "2") (pinfunction "2_2") (pintype "passive"))
      (node (ref "U2") (pin "12") (pinfunction "VIN_12") (pintype "power_in"))
      (node (ref "U2") (pin "13") (pinfunction "VIN_13") (pintype "power_in"))
    )
    (net (code "83") (name "unconnected-(JP1-Pad5)") (class "Default")
      (node (ref "JP1") (pin "5") (pinfunction "5_5") (pintype "passive+no_connect"))
    )
    (net (code "84") (name "unconnected-(JP1-Pad6)") (class "Default")
      (node (ref "JP1") (pin "6") (pinfunction "6_6") (pintype "passive+no_connect"))
    )
    (net (code "85") (name "unconnected-(JP2-Pad5)") (class "Default")
      (node (ref "JP2") (pin "5") (pinfunction "5_5") (pintype "passive+no_connect"))
    )
    (net (code "86") (name "unconnected-(JP2-Pad6)") (class "Default")
      (node (ref "JP2") (pin "6") (pinfunction "6_6") (pintype "passive+no_connect"))
    )
    (net (code "87") (name "unconnected-(U1-P0.5{slash}AD5{slash}ADC13{slash}T3CLKO-Pad61)") (class "Default")
      (node (ref "U1") (pin "61") (pinfunction "P0.5/AD5/ADC13/T3CLKO_61") (pintype "passive"))
    )
    (net (code "88") (name "unconnected-(U1-P0.7{slash}AD7{slash}T4CLKO-Pad63)") (class "Default")
      (node (ref "U1") (pin "63") (pinfunction "P0.7/AD7/T4CLKO_63") (pintype "passive"))
    )
    (net (code "89") (name "unconnected-(U1-P2.4{slash}A12{slash}PWM4{slash}MISO_2{slash}SDA_2{slash}CCP1_2-Pad47)") (class "Default")
      (node (ref "U1") (pin "47") (pinfunction "P2.4/A12/PWM4/MISO_2/SDA_2/CCP1_2_47") (pintype "passive"))
    )
    (net (code "90") (name "unconnected-(U1-P3.3{slash}INT1{slash}CCP0_4{slash}MISO_4{slash}SDA_4-Pad30)") (class "Default")
      (node (ref "U1") (pin "30") (pinfunction "P3.3/INT1/CCP0_4/MISO_4/SDA_4_30") (pintype "passive"))
    )
    (net (code "91") (name "unconnected-(U1-P3.5{slash}T1{slash}T0CLKO{slash}ECI_4{slash}SS_4{slash}PWMFLT-Pad32)") (class "Default")
      (node (ref "U1") (pin "32") (pinfunction "P3.5/T1/T0CLKO/ECI_4/SS_4/PWMFLT_32") (pintype "passive"))
    )
    (net (code "92") (name "unconnected-(U1-P4.0{slash}WR_3{slash}RXD2_2-Pad22)") (class "Default")
      (node (ref "U1") (pin "22") (pinfunction "P4.0/WR_3/RXD2_2_22") (pintype "passive"))
    )
    (net (code "93") (name "unconnected-(U1-P4.4{slash}RD{slash}TXD_4-Pad11)") (class "Default")
      (node (ref "U1") (pin "11") (pinfunction "P4.4/RD/TXD_4_11") (pintype "passive"))
    )
    (net (code "94") (name "unconnected-(U1-P5.4{slash}RST{slash}MCLKO-Pad18)") (class "Default")
      (node (ref "U1") (pin "18") (pinfunction "P5.4/RST/MCLKO_18") (pintype "passive"))
    )
    (net (code "95") (name "unconnected-(U1-P5.5-Pad20)") (class "Default")
      (node (ref "U1") (pin "20") (pinfunction "P5.5_20") (pintype "passive"))
    )
    (net (code "96") (name "unconnected-(U1-P6.0{slash}PWM0_3-Pad6)") (class "Default")
      (node (ref "U1") (pin "6") (pinfunction "P6.0/PWM0_3_6") (pintype "passive"))
    )
    (net (code "97") (name "unconnected-(U1-P6.3{slash}PWM3_3-Pad9)") (class "Default")
      (node (ref "U1") (pin "9") (pinfunction "P6.3/PWM3_3_9") (pintype "passive"))
    )
    (net (code "98") (name "unconnected-(U1-P6.4{slash}PWM4_3-Pad23)") (class "Default")
      (node (ref "U1") (pin "23") (pinfunction "P6.4/PWM4_3_23") (pintype "passive"))
    )
    (net (code "99") (name "unconnected-(U1-P6.5{slash}PWM5_3-Pad24)") (class "Default")
      (node (ref "U1") (pin "24") (pinfunction "P6.5/PWM5_3_24") (pintype "passive"))
    )
    (net (code "100") (name "unconnected-(U1-P6.6{slash}PWM6_3-Pad25)") (class "Default")
      (node (ref "U1") (pin "25") (pinfunction "P6.6/PWM6_3_25") (pintype "passive"))
    )
    (net (code "101") (name "unconnected-(U1-P7.1{slash}CCP1_3-Pad39)") (class "Default")
      (node (ref "U1") (pin "39") (pinfunction "P7.1/CCP1_3_39") (pintype "passive"))
    )
    (net (code "102") (name "unconnected-(U1-P7.2{slash}CCP2_3-Pad40)") (class "Default")
      (node (ref "U1") (pin "40") (pinfunction "P7.2/CCP2_3_40") (pintype "passive"))
    )
    (net (code "103") (name "unconnected-(U1-P7.3{slash}CCP3_3-Pad41)") (class "Default")
      (node (ref "U1") (pin "41") (pinfunction "P7.3/CCP3_3_41") (pintype "passive"))
    )
  )
)
